# OnkoMain.net
KiCad netlist of a schematic drawn in Altium Designer
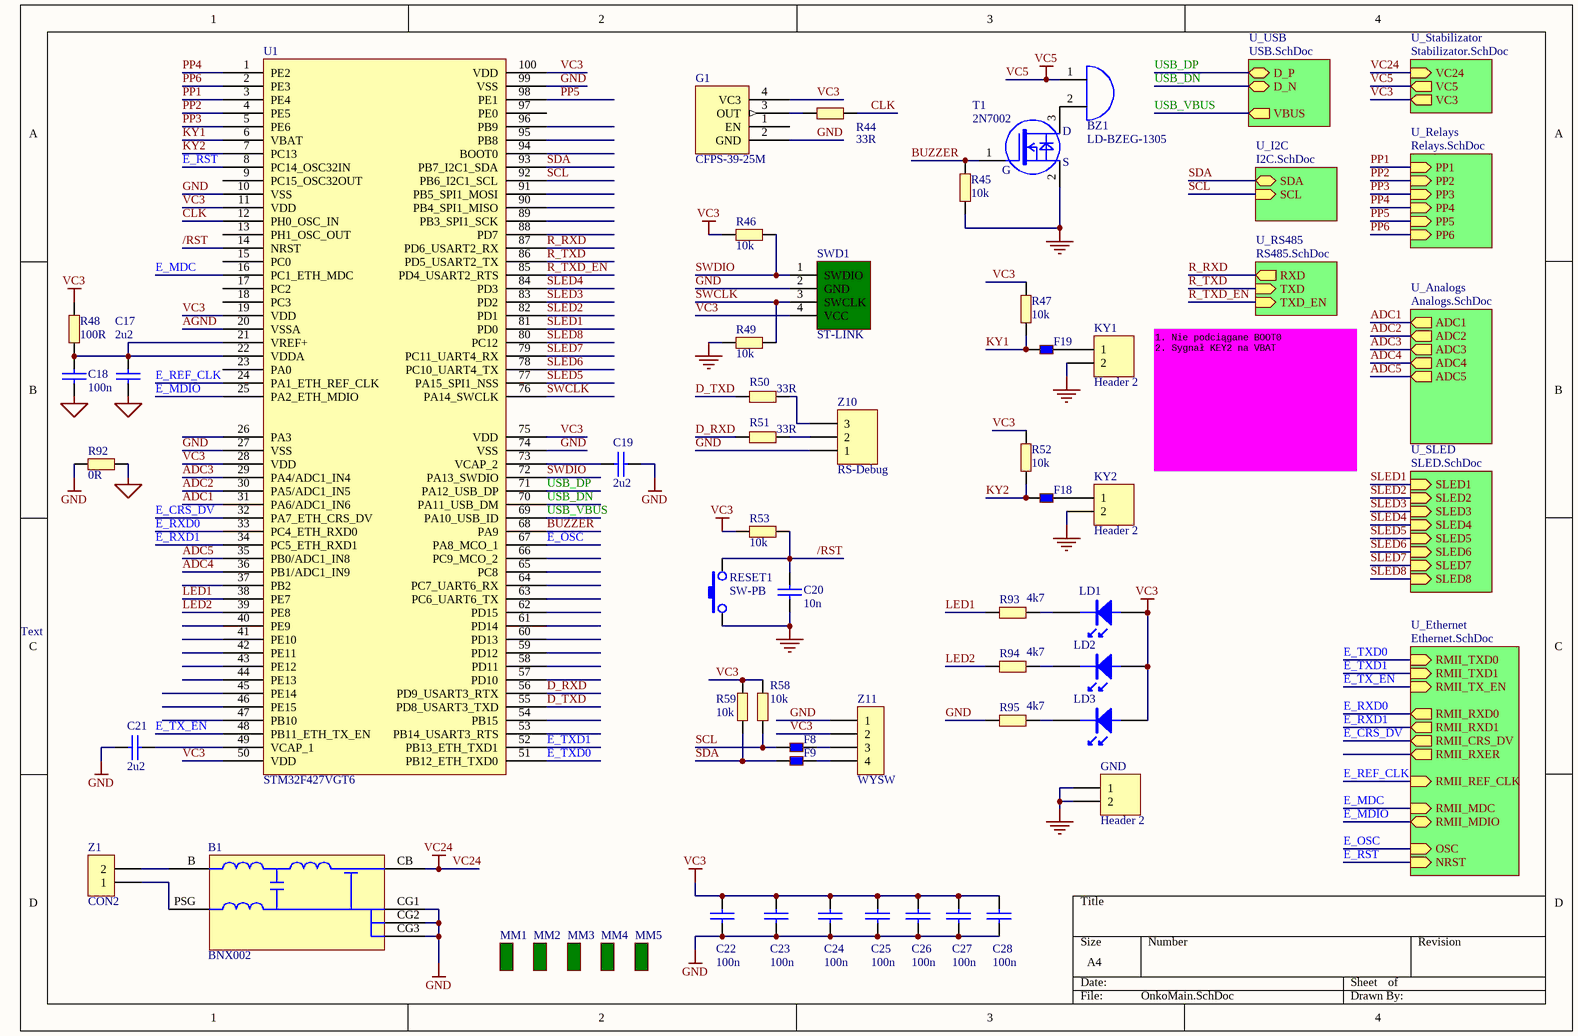
[diagram p0: OnkoMain.SchDoc]

(export (version "E")
  (design (tool "Eeschema 10.0.6"))
  (components
    (comp (ref "B1") (value "BNX002") (footprint "BNX002") (libsource (lib "ElhosSchLib") (part "BNX002")))
    (comp (ref "BZ1") (value "LD-BZEG-1305") (footprint "LD-BZEG-1305") (libsource (lib "*") (part "BUZZER")))
    (comp (ref "C17")
      (value "2u2")
      (footprint "0805C")
      (description "Capacitor")
      (libsource (lib "*") (part "CAP"))
    )
    (comp (ref "C18")
      (value "100n")
      (footprint "0805C")
      (description "Capacitor")
      (libsource (lib "*") (part "CAP"))
    )
    (comp (ref "C19")
      (value "2u2")
      (footprint "0805C")
      (description "Capacitor")
      (libsource (lib "*") (part "CAP"))
    )
    (comp (ref "C20")
      (value "10n")
      (footprint "0805C")
      (description "Capacitor")
      (libsource (lib "*") (part "CAP"))
    )
    (comp (ref "C21")
      (value "2u2")
      (footprint "0805C")
      (description "Capacitor")
      (libsource (lib "*") (part "CAP"))
    )
    (comp (ref "C22")
      (value "100n")
      (footprint "0805C")
      (description "Capacitor")
      (libsource (lib "*") (part "CAP"))
    )
    (comp (ref "C23")
      (value "100n")
      (footprint "0805C")
      (description "Capacitor")
      (libsource (lib "*") (part "CAP"))
    )
    (comp (ref "C24")
      (value "100n")
      (footprint "0805C")
      (description "Capacitor")
      (libsource (lib "*") (part "CAP"))
    )
    (comp (ref "C25")
      (value "100n")
      (footprint "0805C")
      (description "Capacitor")
      (libsource (lib "*") (part "CAP"))
    )
    (comp (ref "C26")
      (value "100n")
      (footprint "0805C")
      (description "Capacitor")
      (libsource (lib "*") (part "CAP"))
    )
    (comp (ref "C27")
      (value "100n")
      (footprint "0805C")
      (description "Capacitor")
      (libsource (lib "*") (part "CAP"))
    )
    (comp (ref "C28")
      (value "100n")
      (footprint "0805C")
      (description "Capacitor")
      (libsource (lib "*") (part "CAP"))
    )
    (comp (ref "F8")
      (value "BLM18BB141SN1D")
      (footprint "0805L")
      (description "Koralik ferrytowy")
      (libsource (lib "*") (part "1812"))
    )
    (comp (ref "F9")
      (value "BLM18BB141SN1D")
      (footprint "0805L")
      (description "Koralik ferrytowy")
      (libsource (lib "*") (part "1812"))
    )
    (comp (ref "F18")
      (value "BLM18BB141SN1D")
      (footprint "0805L")
      (description "Koralik ferrytowy")
      (libsource (lib "*") (part "1812"))
    )
    (comp (ref "F19")
      (value "BLM18BB141SN1D")
      (footprint "0805L")
      (description "Koralik ferrytowy")
      (libsource (lib "*") (part "1812"))
    )
    (comp (ref "G1") (value "CFPS-39-25M") (footprint "GEN_SMD1_1") (libsource (lib "*") (part "GENER_SMD")))
    (comp (ref "GND")
      (value "Header 2")
      (footprint "HDR1X2")
      (description "Header, 2-Pin")
      (fields (field (name "PUBLISHER") "Altium Limited"))
      (libsource (lib "Miscellaneous Connectors") (part "Header 2"))
    )
    (comp (ref "KY1")
      (value "Header 2")
      (footprint "HDR1X2")
      (description "Header, 2-Pin")
      (fields (field (name "PUBLISHER") "Altium Limited"))
      (libsource (lib "Miscellaneous Connectors") (part "Header 2"))
    )
    (comp (ref "KY2")
      (value "Header 2")
      (footprint "HDR1X2")
      (description "Header, 2-Pin")
      (fields (field (name "PUBLISHER") "Altium Limited"))
      (libsource (lib "Miscellaneous Connectors") (part "Header 2"))
    )
    (comp (ref "LD1") (value "~") (footprint "0805LG") (libsource (lib "*") (part "LED")))
    (comp (ref "LD2") (value "~") (footprint "0805LR") (libsource (lib "*") (part "LED")))
    (comp (ref "LD3") (value "~") (footprint "0805LG") (libsource (lib "*") (part "LED")))
    (comp (ref "MM1") (value "~") (footprint "REF_CIR") (libsource (lib "*") (part "MECH")))
    (comp (ref "MM2") (value "~") (footprint "REF_CIR") (libsource (lib "*") (part "MECH")))
    (comp (ref "MM3") (value "~") (footprint "REF_SQR") (libsource (lib "*") (part "MECH")))
    (comp (ref "MM4") (value "~") (footprint "REF_SQR") (libsource (lib "*") (part "MECH")))
    (comp (ref "MM5") (value "~") (footprint "PB_FREE_GRAF") (libsource (lib "*") (part "MECH")))
    (comp (ref "R44") (value "33R") (footprint "0805R") (libsource (lib "") (part "RES3_1")))
    (comp (ref "R45") (value "10k") (footprint "0805") (libsource (lib "") (part "RES3_3")))
    (comp (ref "R46") (value "10k") (footprint "0805R") (libsource (lib "") (part "RES3_2")))
    (comp (ref "R47") (value "10k") (footprint "0805R") (libsource (lib "") (part "RES3_1")))
    (comp (ref "R48") (value "100R") (footprint "0805") (libsource (lib "") (part "RES3_1")))
    (comp (ref "R49") (value "10k") (footprint "0805R") (libsource (lib "") (part "RES3_2")))
    (comp (ref "R50") (value "33R") (footprint "0805R") (libsource (lib "*") (part "RES3")))
    (comp (ref "R51") (value "33R") (footprint "0805R") (libsource (lib "*") (part "RES3")))
    (comp (ref "R52") (value "10k") (footprint "0805R") (libsource (lib "") (part "RES3_1")))
    (comp (ref "R53") (value "10k") (footprint "0805R") (libsource (lib "") (part "RES3_2")))
    (comp (ref "R58") (value "10k") (footprint "0805R") (libsource (lib "") (part "RES3_1")))
    (comp (ref "R59") (value "10k") (footprint "0805R") (libsource (lib "") (part "RES3_1")))
    (comp (ref "R92") (value "0R") (footprint "0805") (libsource (lib "*") (part "RES3")))
    (comp (ref "R93") (value "4k7") (footprint "0805R") (libsource (lib "*") (part "RES3")))
    (comp (ref "R94") (value "4k7") (footprint "0805R") (libsource (lib "*") (part "RES3")))
    (comp (ref "R95") (value "4k7") (footprint "0805R") (libsource (lib "*") (part "RES3")))
    (comp (ref "RESET1") (value "SW-PB") (footprint "DTSM31N_2") (libsource (lib "*") (part "SW-PB")))
    (comp (ref "SWD1")
      (value "ST-LINK")
      (footprint "PIN4")
      (description "Header, 4-Pin")
      (fields (field (name "PUBLISHER") "Altium Limited"))
      (libsource (lib "GkSchlib") (part "SW_CON"))
    )
    (comp (ref "T1") (value "2N7002") (footprint "SOT23") (libsource (lib "GkSchlib") (part "MOSFET-P_1_1")))
    (comp (ref "U1")
      (value "STM32F427VGT6")
      (footprint "VQ100_2")
      (libsource (lib "GkSchlib") (part "STM32F427_LQFP100"))
    )
    (comp (ref "Z1")
      (value "CON2")
      (footprint "ARC-L-2-5.08")
      (description "Connector")
      (libsource (lib "*") (part "CON2"))
    )
    (comp (ref "Z10")
      (value "RS-Debug")
      (footprint "PIN3")
      (description "Header, 3-Pin")
      (fields (field (name "PUBLISHER") "Altium Limited"))
      (libsource (lib "Miscellaneous Connectors") (part "Header 3"))
    )
    (comp (ref "Z11")
      (value "WYSW")
      (footprint "PIN4")
      (description "Connector")
      (libsource (lib "*") (part "CON4"))
    )
  )
  (nets
    (net (code "1") (name "/ADC1") (class "Default")
      (node (ref "U1") (pin "31") (pinfunction "PA6/ADC1_IN6_31") (pintype "passive"))
    )
    (net (code "2") (name "/ADC2") (class "Default")
      (node (ref "U1") (pin "30") (pinfunction "PA5/ADC1_IN5_30") (pintype "passive"))
    )
    (net (code "3") (name "/ADC3") (class "Default")
      (node (ref "U1") (pin "29") (pinfunction "PA4/ADC1_IN4_29") (pintype "passive"))
    )
    (net (code "4") (name "/ADC4") (class "Default")
      (node (ref "U1") (pin "36") (pinfunction "PB1/ADC1_IN9_36") (pintype "passive"))
    )
    (net (code "5") (name "/ADC5") (class "Default")
      (node (ref "U1") (pin "35") (pinfunction "PB0/ADC1_IN8_35") (pintype "passive"))
    )
    (net (code "6") (name "/BUZZER") (class "Default")
      (node (ref "R45") (pin "1") (pintype "passive"))
      (node (ref "T1") (pin "1") (pinfunction "1_1") (pintype "passive"))
      (node (ref "U1") (pin "68") (pinfunction "PA9_68") (pintype "passive"))
    )
    (net (code "7") (name "/CLK") (class "Default")
      (node (ref "R44") (pin "2") (pintype "passive"))
      (node (ref "U1") (pin "12") (pinfunction "PH0_OSC_IN_12") (pintype "passive"))
    )
    (net (code "8") (name "/D_RXD") (class "Default")
      (node (ref "R51") (pin "2") (pintype "passive"))
      (node (ref "U1") (pin "56") (pinfunction "PD9_USART3_RTX_56") (pintype "passive"))
    )
    (net (code "9") (name "/D_TXD") (class "Default")
      (node (ref "R50") (pin "2") (pintype "passive"))
      (node (ref "U1") (pin "55") (pinfunction "PD8_USART3_TXD_55") (pintype "passive"))
    )
    (net (code "10") (name "/E_CRS_DV") (class "Default")
      (node (ref "U1") (pin "32") (pinfunction "PA7_ETH_CRS_DV_32") (pintype "passive"))
    )
    (net (code "11") (name "/E_MDC") (class "Default")
      (node (ref "U1") (pin "16") (pinfunction "PC1_ETH_MDC_16") (pintype "passive"))
    )
    (net (code "12") (name "/E_MDIO") (class "Default")
      (node (ref "U1") (pin "25") (pinfunction "PA2_ETH_MDIO_25") (pintype "passive"))
    )
    (net (code "13") (name "/E_OSC") (class "Default")
      (node (ref "U1") (pin "67") (pinfunction "PA8_MCO_1_67") (pintype "passive"))
    )
    (net (code "14") (name "/E_REF_CLK") (class "Default")
      (node (ref "U1") (pin "24") (pinfunction "PA1_ETH_REF_CLK_24") (pintype "passive"))
    )
    (net (code "15") (name "/E_RST") (class "Default")
      (node (ref "U1") (pin "8") (pinfunction "PC14_OSC32IN_8") (pintype "passive"))
    )
    (net (code "16") (name "/E_RXD0") (class "Default")
      (node (ref "U1") (pin "33") (pinfunction "PC4_ETH_RXD0_33") (pintype "passive"))
    )
    (net (code "17") (name "/E_RXD1") (class "Default")
      (node (ref "U1") (pin "34") (pinfunction "PC5_ETH_RXD1_34") (pintype "passive"))
    )
    (net (code "18") (name "/E_TXD0") (class "Default")
      (node (ref "U1") (pin "51") (pinfunction "PB12_ETH_TXD0_51") (pintype "passive"))
    )
    (net (code "19") (name "/E_TXD1") (class "Default")
      (node (ref "U1") (pin "52") (pinfunction "PB13_ETH_TXD1_52") (pintype "passive"))
    )
    (net (code "20") (name "/E_TX_EN") (class "Default")
      (node (ref "U1") (pin "48") (pinfunction "PB11_ETH_TX_EN_48") (pintype "passive"))
    )
    (net (code "21") (name "/KY1") (class "Default")
      (node (ref "F19") (pin "2") (pintype "passive"))
      (node (ref "R47") (pin "1") (pintype "passive"))
      (node (ref "U1") (pin "6") (pinfunction "VBAT_6") (pintype "passive"))
    )
    (net (code "22") (name "/KY2") (class "Default")
      (node (ref "F18") (pin "2") (pintype "passive"))
      (node (ref "R52") (pin "1") (pintype "passive"))
      (node (ref "U1") (pin "7") (pinfunction "PC13_7") (pintype "passive"))
    )
    (net (code "23") (name "/LED1") (class "Default")
      (node (ref "R93") (pin "2") (pintype "passive"))
      (node (ref "U1") (pin "38") (pinfunction "PE7_38") (pintype "passive"))
    )
    (net (code "24") (name "/LED2") (class "Default")
      (node (ref "R94") (pin "2") (pintype "passive"))
      (node (ref "U1") (pin "39") (pinfunction "PE8_39") (pintype "passive"))
    )
    (net (code "25") (name "/PP1") (class "Default")
      (node (ref "U1") (pin "3") (pinfunction "PE4_3") (pintype "passive"))
    )
    (net (code "26") (name "/PP2") (class "Default")
      (node (ref "U1") (pin "4") (pinfunction "PE5_4") (pintype "passive"))
    )
    (net (code "27") (name "/PP3") (class "Default")
      (node (ref "U1") (pin "5") (pinfunction "PE6_5") (pintype "passive"))
    )
    (net (code "28") (name "/PP4") (class "Default")
      (node (ref "U1") (pin "1") (pinfunction "PE2_1") (pintype "passive"))
    )
    (net (code "29") (name "/PP5") (class "Default")
      (node (ref "U1") (pin "98") (pinfunction "PE1_98") (pintype "passive"))
    )
    (net (code "30") (name "/PP6") (class "Default")
      (node (ref "U1") (pin "2") (pinfunction "PE3_2") (pintype "passive"))
    )
    (net (code "32") (name "/R_RXD") (class "Default")
      (node (ref "U1") (pin "87") (pinfunction "PD6_USART2_RX_87") (pintype "passive"))
    )
    (net (code "33") (name "/R_TXD") (class "Default")
      (node (ref "U1") (pin "86") (pinfunction "PD5_USART2_TX_86") (pintype "passive"))
    )
    (net (code "34") (name "/R_TXD_EN") (class "Default")
      (node (ref "U1") (pin "85") (pinfunction "PD4_USART2_RTS_85") (pintype "passive"))
    )
    (net (code "35") (name "/SCL") (class "Default")
      (node (ref "F8") (pin "2") (pintype "passive"))
      (node (ref "R58") (pin "1") (pintype "passive"))
      (node (ref "U1") (pin "92") (pinfunction "PB6_I2C1_SCL_92") (pintype "passive"))
    )
    (net (code "36") (name "/SDA") (class "Default")
      (node (ref "F9") (pin "2") (pintype "passive"))
      (node (ref "R59") (pin "1") (pintype "passive"))
      (node (ref "U1") (pin "93") (pinfunction "PB7_I2C1_SDA_93") (pintype "passive"))
    )
    (net (code "37") (name "/SLED1") (class "Default")
      (node (ref "U1") (pin "81") (pinfunction "PD0_81") (pintype "passive"))
    )
    (net (code "38") (name "/SLED2") (class "Default")
      (node (ref "U1") (pin "82") (pinfunction "PD1_82") (pintype "passive"))
    )
    (net (code "39") (name "/SLED3") (class "Default")
      (node (ref "U1") (pin "83") (pinfunction "PD2_83") (pintype "passive"))
    )
    (net (code "40") (name "/SLED4") (class "Default")
      (node (ref "U1") (pin "84") (pinfunction "PD3_84") (pintype "passive"))
    )
    (net (code "41") (name "/SLED5") (class "Default")
      (node (ref "U1") (pin "77") (pinfunction "PA15_SPI1_NSS_77") (pintype "passive"))
    )
    (net (code "42") (name "/SLED6") (class "Default")
      (node (ref "U1") (pin "78") (pinfunction "PC10_UART4_TX_78") (pintype "passive"))
    )
    (net (code "43") (name "/SLED7") (class "Default")
      (node (ref "U1") (pin "79") (pinfunction "PC11_UART4_RX_79") (pintype "passive"))
    )
    (net (code "44") (name "/SLED8") (class "Default")
      (node (ref "U1") (pin "80") (pinfunction "PC12_80") (pintype "passive"))
    )
    (net (code "45") (name "/SWCLK") (class "Default")
      (node (ref "R49") (pin "2") (pintype "passive"))
      (node (ref "SWD1") (pin "3") (pinfunction "SWCLK_3") (pintype "passive"))
      (node (ref "U1") (pin "76") (pinfunction "PA14_SWCLK_76") (pintype "passive"))
    )
    (net (code "46") (name "/SWDIO") (class "Default")
      (node (ref "R46") (pin "2") (pintype "passive"))
      (node (ref "SWD1") (pin "1") (pinfunction "SWDIO_1") (pintype "passive"))
      (node (ref "U1") (pin "72") (pinfunction "PA13_SWDIO_72") (pintype "passive"))
    )
    (net (code "47") (name "/USB_DN") (class "Default")
      (node (ref "U1") (pin "70") (pinfunction "PA11_USB_DM_70") (pintype "passive"))
    )
    (net (code "48") (name "/USB_DP") (class "Default")
      (node (ref "U1") (pin "71") (pinfunction "PA12_USB_DP_71") (pintype "passive"))
    )
    (net (code "49") (name "/USB_VBUS") (class "Default")
      (node (ref "U1") (pin "69") (pinfunction "PA10_USB_ID_69") (pintype "passive"))
    )
    (net (code "50") (name "/{slash}RST") (class "Default")
      (node (ref "C20") (pin "1") (pinfunction "1_1") (pintype "passive"))
      (node (ref "R53") (pin "2") (pintype "passive"))
      (node (ref "RESET1") (pin "2") (pinfunction "2_2") (pintype "passive"))
      (node (ref "U1") (pin "14") (pinfunction "NRST_14") (pintype "passive"))
    )
    (net (code "51") (name "AGND") (class "Default")
      (node (ref "C17") (pin "2") (pinfunction "2_2") (pintype "passive"))
      (node (ref "C18") (pin "2") (pinfunction "2_2") (pintype "passive"))
      (node (ref "R92") (pin "1") (pintype "passive"))
      (node (ref "U1") (pin "20") (pinfunction "VSSA_20") (pintype "passive"))
    )
    (net (code "52") (name "GND") (class "Default")
      (node (ref "B1") (pin "CG1") (pintype "passive"))
      (node (ref "B1") (pin "CG2") (pintype "passive"))
      (node (ref "B1") (pin "CG3") (pintype "passive"))
      (node (ref "C19") (pin "1") (pinfunction "1_1") (pintype "passive"))
      (node (ref "C20") (pin "2") (pinfunction "2_2") (pintype "passive"))
      (node (ref "C21") (pin "1") (pinfunction "1_1") (pintype "passive"))
      (node (ref "C22") (pin "2") (pinfunction "2_2") (pintype "passive"))
      (node (ref "C23") (pin "2") (pinfunction "2_2") (pintype "passive"))
      (node (ref "C24") (pin "2") (pinfunction "2_2") (pintype "passive"))
      (node (ref "C25") (pin "2") (pinfunction "2_2") (pintype "passive"))
      (node (ref "C26") (pin "2") (pinfunction "2_2") (pintype "passive"))
      (node (ref "C27") (pin "2") (pinfunction "2_2") (pintype "passive"))
      (node (ref "C28") (pin "2") (pinfunction "2_2") (pintype "passive"))
      (node (ref "G1") (pin "2") (pinfunction "GND_2") (pintype "power_in"))
      (node (ref "GND") (pin "1") (pinfunction "1_1") (pintype "passive"))
      (node (ref "GND") (pin "2") (pinfunction "2_2") (pintype "passive"))
      (node (ref "KY1") (pin "2") (pinfunction "2_2") (pintype "passive"))
      (node (ref "KY2") (pin "2") (pinfunction "2_2") (pintype "passive"))
      (node (ref "R45") (pin "2") (pintype "passive"))
      (node (ref "R49") (pin "1") (pintype "passive"))
      (node (ref "R92") (pin "2") (pintype "passive"))
      (node (ref "R95") (pin "2") (pintype "passive"))
      (node (ref "RESET1") (pin "1") (pinfunction "1_1") (pintype "passive"))
      (node (ref "SWD1") (pin "2") (pinfunction "GND_2") (pintype "passive"))
      (node (ref "T1") (pin "2") (pinfunction "S_2") (pintype "passive"))
      (node (ref "U1") (pin "10") (pinfunction "VSS_10") (pintype "passive"))
      (node (ref "U1") (pin "27") (pinfunction "VSS_27") (pintype "passive"))
      (node (ref "U1") (pin "74") (pinfunction "VSS_74") (pintype "passive"))
      (node (ref "U1") (pin "99") (pinfunction "VSS_99") (pintype "passive"))
      (node (ref "Z10") (pin "1") (pinfunction "1_1") (pintype "passive"))
      (node (ref "Z11") (pin "1") (pinfunction "1_1") (pintype "passive"))
    )
    (net (code "53") (name "Net-(B1-PadB)") (class "Default")
      (node (ref "B1") (pin "B") (pintype "passive"))
      (node (ref "Z1") (pin "2") (pinfunction "2_2") (pintype "passive"))
    )
    (net (code "54") (name "Net-(B1-PadPSG)") (class "Default")
      (node (ref "B1") (pin "PSG") (pintype "passive"))
      (node (ref "Z1") (pin "1") (pinfunction "1_1") (pintype "passive"))
    )
    (net (code "55") (name "Net-(F8-Pad1)") (class "Default")
      (node (ref "F8") (pin "1") (pintype "passive"))
      (node (ref "Z11") (pin "3") (pinfunction "3_3") (pintype "passive"))
    )
    (net (code "56") (name "Net-(F9-Pad1)") (class "Default")
      (node (ref "F9") (pin "1") (pintype "passive"))
      (node (ref "Z11") (pin "4") (pinfunction "4_4") (pintype "passive"))
    )
    (net (code "57") (name "Net-(F18-Pad1)") (class "Default")
      (node (ref "F18") (pin "1") (pintype "passive"))
      (node (ref "KY2") (pin "1") (pinfunction "1_1") (pintype "passive"))
    )
    (net (code "58") (name "Net-(F19-Pad1)") (class "Default")
      (node (ref "F19") (pin "1") (pintype "passive"))
      (node (ref "KY1") (pin "1") (pinfunction "1_1") (pintype "passive"))
    )
    (net (code "59") (name "Net-(G1-OUT)") (class "Default")
      (node (ref "G1") (pin "3") (pinfunction "OUT_3") (pintype "output"))
      (node (ref "R44") (pin "1") (pintype "passive"))
    )
    (net (code "60") (name "Net-(LD1-2)") (class "Default")
      (node (ref "LD1") (pin "K") (pinfunction "2_K") (pintype "passive"))
      (node (ref "R93") (pin "1") (pintype "passive"))
    )
    (net (code "61") (name "Net-(LD2-2)") (class "Default")
      (node (ref "LD2") (pin "K") (pinfunction "2_K") (pintype "passive"))
      (node (ref "R94") (pin "1") (pintype "passive"))
    )
    (net (code "62") (name "Net-(LD3-2)") (class "Default")
      (node (ref "LD3") (pin "K") (pinfunction "2_K") (pintype "passive"))
      (node (ref "R95") (pin "1") (pintype "passive"))
    )
    (net (code "63") (name "Net-(R50-Pad1)") (class "Default")
      (node (ref "R50") (pin "1") (pintype "passive"))
      (node (ref "Z10") (pin "3") (pinfunction "3_3") (pintype "passive"))
    )
    (net (code "64") (name "Net-(R51-Pad1)") (class "Default")
      (node (ref "R51") (pin "1") (pintype "passive"))
      (node (ref "Z10") (pin "2") (pinfunction "2_2") (pintype "passive"))
    )
    (net (code "65") (name "Net-(T1-D)") (class "Default")
      (node (ref "BZ1") (pin "2") (pinfunction "2_2") (pintype "passive"))
      (node (ref "T1") (pin "3") (pinfunction "D_3") (pintype "passive"))
    )
    (net (code "66") (name "Net-(U1-VCAP_1)") (class "Default")
      (node (ref "C21") (pin "2") (pinfunction "2_2") (pintype "passive"))
      (node (ref "U1") (pin "49") (pinfunction "VCAP_1_49") (pintype "passive"))
    )
    (net (code "67") (name "Net-(U1-VCAP_2)") (class "Default")
      (node (ref "C19") (pin "2") (pinfunction "2_2") (pintype "passive"))
      (node (ref "U1") (pin "73") (pinfunction "VCAP_2_73") (pintype "passive"))
    )
    (net (code "68") (name "Net-(U1-VDDA)") (class "Default")
      (node (ref "C17") (pin "1") (pinfunction "1_1") (pintype "passive"))
      (node (ref "C18") (pin "1") (pinfunction "1_1") (pintype "passive"))
      (node (ref "R48") (pin "1") (pintype "passive"))
      (node (ref "U1") (pin "21") (pinfunction "VREF+_21") (pintype "passive"))
      (node (ref "U1") (pin "22") (pinfunction "VDDA_22") (pintype "passive"))
    )
    (net (code "69") (name "VC3") (class "Default")
      (node (ref "C22") (pin "1") (pinfunction "1_1") (pintype "passive"))
      (node (ref "C23") (pin "1") (pinfunction "1_1") (pintype "passive"))
      (node (ref "C24") (pin "1") (pinfunction "1_1") (pintype "passive"))
      (node (ref "C25") (pin "1") (pinfunction "1_1") (pintype "passive"))
      (node (ref "C26") (pin "1") (pinfunction "1_1") (pintype "passive"))
      (node (ref "C27") (pin "1") (pinfunction "1_1") (pintype "passive"))
      (node (ref "C28") (pin "1") (pinfunction "1_1") (pintype "passive"))
      (node (ref "G1") (pin "4") (pinfunction "VC3_4") (pintype "power_in"))
      (node (ref "LD1") (pin "A") (pinfunction "1_A") (pintype "passive"))
      (node (ref "LD2") (pin "A") (pinfunction "1_A") (pintype "passive"))
      (node (ref "LD3") (pin "A") (pinfunction "1_A") (pintype "passive"))
      (node (ref "R46") (pin "1") (pintype "passive"))
      (node (ref "R47") (pin "2") (pintype "passive"))
      (node (ref "R48") (pin "2") (pintype "passive"))
      (node (ref "R52") (pin "2") (pintype "passive"))
      (node (ref "R53") (pin "1") (pintype "passive"))
      (node (ref "R58") (pin "2") (pintype "passive"))
      (node (ref "R59") (pin "2") (pintype "passive"))
      (node (ref "SWD1") (pin "4") (pinfunction "VCC_4") (pintype "passive"))
      (node (ref "U1") (pin "100") (pinfunction "VDD_100") (pintype "passive"))
      (node (ref "U1") (pin "11") (pinfunction "VDD_11") (pintype "passive"))
      (node (ref "U1") (pin "19") (pinfunction "VDD_19") (pintype "passive"))
      (node (ref "U1") (pin "28") (pinfunction "VDD_28") (pintype "passive"))
      (node (ref "U1") (pin "50") (pinfunction "VDD_50") (pintype "passive"))
      (node (ref "U1") (pin "75") (pinfunction "VDD_75") (pintype "passive"))
      (node (ref "Z11") (pin "2") (pinfunction "2_2") (pintype "passive"))
    )
    (net (code "70") (name "VC5") (class "Default")
      (node (ref "BZ1") (pin "1") (pinfunction "1_1") (pintype "passive"))
    )
    (net (code "71") (name "VC24") (class "Default") (node (ref "B1") (pin "CB") (pintype "passive")))
    (net (code "72") (name "unconnected-(G1-EN-Pad1)") (class "Default")
      (node (ref "G1") (pin "1") (pinfunction "EN_1") (pintype "passive"))
    )
    (net (code "73") (name "unconnected-(U1-BOOT0-Pad94)") (class "Default")
      (node (ref "U1") (pin "94") (pinfunction "BOOT0_94") (pintype "passive"))
    )
    (net (code "74") (name "unconnected-(U1-PA0-Pad23)") (class "Default")
      (node (ref "U1") (pin "23") (pinfunction "PA0_23") (pintype "passive"))
    )
    (net (code "75") (name "unconnected-(U1-PA3-Pad26)") (class "Default")
      (node (ref "U1") (pin "26") (pinfunction "PA3_26") (pintype "passive"))
    )
    (net (code "76") (name "unconnected-(U1-PB2-Pad37)") (class "Default")
      (node (ref "U1") (pin "37") (pinfunction "PB2_37") (pintype "passive"))
    )
    (net (code "77") (name "unconnected-(U1-PB3_SPI1_SCK-Pad89)") (class "Default")
      (node (ref "U1") (pin "89") (pinfunction "PB3_SPI1_SCK_89") (pintype "passive"))
    )
    (net (code "78") (name "unconnected-(U1-PB4_SPI1_MISO-Pad90)") (class "Default")
      (node (ref "U1") (pin "90") (pinfunction "PB4_SPI1_MISO_90") (pintype "passive"))
    )
    (net (code "79") (name "unconnected-(U1-PB5_SPI1_MOSI-Pad91)") (class "Default")
      (node (ref "U1") (pin "91") (pinfunction "PB5_SPI1_MOSI_91") (pintype "passive"))
    )
    (net (code "80") (name "unconnected-(U1-PB8-Pad95)") (class "Default")
      (node (ref "U1") (pin "95") (pinfunction "PB8_95") (pintype "passive"))
    )
    (net (code "81") (name "unconnected-(U1-PB9-Pad96)") (class "Default")
      (node (ref "U1") (pin "96") (pinfunction "PB9_96") (pintype "passive"))
    )
    (net (code "82") (name "unconnected-(U1-PB10-Pad47)") (class "Default")
      (node (ref "U1") (pin "47") (pinfunction "PB10_47") (pintype "passive"))
    )
    (net (code "83") (name "unconnected-(U1-PB14_USART3_RTS-Pad53)") (class "Default")
      (node (ref "U1") (pin "53") (pinfunction "PB14_USART3_RTS_53") (pintype "passive"))
    )
    (net (code "84") (name "unconnected-(U1-PB15-Pad54)") (class "Default")
      (node (ref "U1") (pin "54") (pinfunction "PB15_54") (pintype "passive"))
    )
    (net (code "85") (name "unconnected-(U1-PC0-Pad15)") (class "Default")
      (node (ref "U1") (pin "15") (pinfunction "PC0_15") (pintype "passive"))
    )
    (net (code "86") (name "unconnected-(U1-PC2-Pad17)") (class "Default")
      (node (ref "U1") (pin "17") (pinfunction "PC2_17") (pintype "passive"))
    )
    (net (code "87") (name "unconnected-(U1-PC3-Pad18)") (class "Default")
      (node (ref "U1") (pin "18") (pinfunction "PC3_18") (pintype "passive"))
    )
    (net (code "88") (name "unconnected-(U1-PC6_UART6_TX-Pad63)") (class "Default")
      (node (ref "U1") (pin "63") (pinfunction "PC6_UART6_TX_63") (pintype "passive"))
    )
    (net (code "89") (name "unconnected-(U1-PC7_UART6_RX-Pad64)") (class "Default")
      (node (ref "U1") (pin "64") (pinfunction "PC7_UART6_RX_64") (pintype "passive"))
    )
    (net (code "90") (name "unconnected-(U1-PC8-Pad65)") (class "Default")
      (node (ref "U1") (pin "65") (pinfunction "PC8_65") (pintype "passive"))
    )
    (net (code "91") (name "unconnected-(U1-PC9_MCO_2-Pad66)") (class "Default")
      (node (ref "U1") (pin "66") (pinfunction "PC9_MCO_2_66") (pintype "passive"))
    )
    (net (code "92") (name "unconnected-(U1-PC15_OSC32OUT-Pad9)") (class "Default")
      (node (ref "U1") (pin "9") (pinfunction "PC15_OSC32OUT_9") (pintype "passive"))
    )
    (net (code "93") (name "unconnected-(U1-PD7-Pad88)") (class "Default")
      (node (ref "U1") (pin "88") (pinfunction "PD7_88") (pintype "passive"))
    )
    (net (code "94") (name "unconnected-(U1-PD10-Pad57)") (class "Default")
      (node (ref "U1") (pin "57") (pinfunction "PD10_57") (pintype "passive"))
    )
    (net (code "95") (name "unconnected-(U1-PD11-Pad58)") (class "Default")
      (node (ref "U1") (pin "58") (pinfunction "PD11_58") (pintype "passive"))
    )
    (net (code "96") (name "unconnected-(U1-PD12-Pad59)") (class "Default")
      (node (ref "U1") (pin "59") (pinfunction "PD12_59") (pintype "passive"))
    )
    (net (code "97") (name "unconnected-(U1-PD13-Pad60)") (class "Default")
      (node (ref "U1") (pin "60") (pinfunction "PD13_60") (pintype "passive"))
    )
    (net (code "98") (name "unconnected-(U1-PD14-Pad61)") (class "Default")
      (node (ref "U1") (pin "61") (pinfunction "PD14_61") (pintype "passive"))
    )
    (net (code "99") (name "unconnected-(U1-PD15-Pad62)") (class "Default")
      (node (ref "U1") (pin "62") (pinfunction "PD15_62") (pintype "passive"))
    )
    (net (code "100") (name "unconnected-(U1-PE0-Pad97)") (class "Default")
      (node (ref "U1") (pin "97") (pinfunction "PE0_97") (pintype "passive"))
    )
    (net (code "101") (name "unconnected-(U1-PE9-Pad40)") (class "Default")
      (node (ref "U1") (pin "40") (pinfunction "PE9_40") (pintype "passive"))
    )
    (net (code "102") (name "unconnected-(U1-PE10-Pad41)") (class "Default")
      (node (ref "U1") (pin "41") (pinfunction "PE10_41") (pintype "passive"))
    )
    (net (code "103") (name "unconnected-(U1-PE11-Pad42)") (class "Default")
      (node (ref "U1") (pin "42") (pinfunction "PE11_42") (pintype "passive"))
    )
    (net (code "104") (name "unconnected-(U1-PE12-Pad43)") (class "Default")
      (node (ref "U1") (pin "43") (pinfunction "PE12_43") (pintype "passive"))
    )
    (net (code "105") (name "unconnected-(U1-PE13-Pad44)") (class "Default")
      (node (ref "U1") (pin "44") (pinfunction "PE13_44") (pintype "passive"))
    )
    (net (code "106") (name "unconnected-(U1-PE14-Pad45)") (class "Default")
      (node (ref "U1") (pin "45") (pinfunction "PE14_45") (pintype "passive"))
    )
    (net (code "107") (name "unconnected-(U1-PE15-Pad46)") (class "Default")
      (node (ref "U1") (pin "46") (pinfunction "PE15_46") (pintype "passive"))
    )
    (net (code "108") (name "unconnected-(U1-PH1_OSC_OUT-Pad13)") (class "Default")
      (node (ref "U1") (pin "13") (pinfunction "PH1_OSC_OUT_13") (pintype "passive"))
    )
  )
)
